# Sheet1.net
KiCad netlist of a schematic drawn in Altium Designer
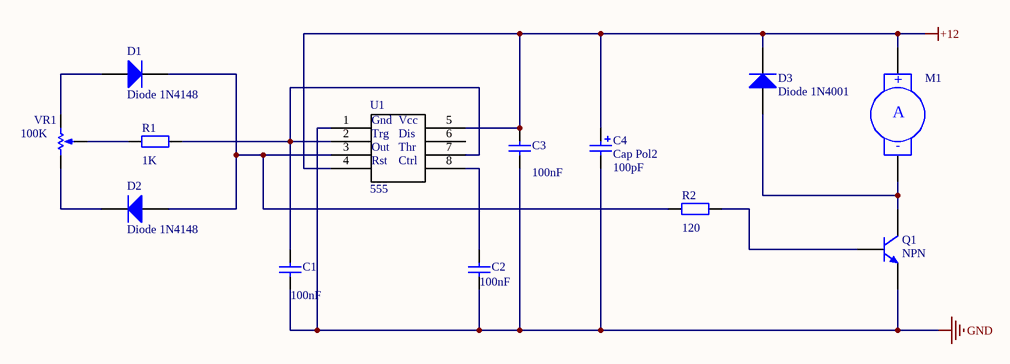
[diagram p0: Sheet1.SchDoc]

(export (version "E")
  (design (tool "Eeschema 10.0.6"))
  (components
    (comp (ref "C1")
      (value "100nF")
      (footprint "RAD-0.3")
      (description "Capacitor")
      (fields (field (name "Comment") "Cap") (field (name "PUBLISHER") "Altium Limited"))
      (libsource (lib "Miscellaneous Devices") (part "Cap"))
    )
    (comp (ref "C2")
      (value "100nF")
      (footprint "RAD-0.3")
      (description "Capacitor")
      (fields (field (name "Comment") "Cap") (field (name "PUBLISHER") "Altium Limited"))
      (libsource (lib "Miscellaneous Devices") (part "Cap"))
    )
    (comp (ref "C3")
      (value "100nF")
      (footprint "RAD-0.3")
      (description "Capacitor")
      (fields (field (name "Comment") "Cap") (field (name "PUBLISHER") "Altium Limited"))
      (libsource (lib "Miscellaneous Devices") (part "Cap"))
    )
    (comp (ref "C4")
      (value "Cap Pol2")
      (footprint "POLAR0.8")
      (description "Polarized Capacitor (Axial)")
      (fields (field (name "ALTIUM_VALUE") "100pF") (field (name "PUBLISHER") "Altium Limited"))
      (libsource (lib "Miscellaneous Devices") (part "Cap Pol2"))
    )
    (comp (ref "D1")
      (value "Diode 1N4148")
      (footprint "DO-35")
      (description "High Conductance Fast Diode")
      (fields (field (name "PUBLISHER") "Altium Limited"))
      (libsource (lib "Miscellaneous Devices") (part "Diode 1N4148"))
    )
    (comp (ref "D2")
      (value "Diode 1N4148")
      (footprint "DO-35")
      (description "High Conductance Fast Diode")
      (fields (field (name "PUBLISHER") "Altium Limited"))
      (libsource (lib "Miscellaneous Devices") (part "Diode 1N4148"))
    )
    (comp (ref "D3")
      (value "Diode 1N4001")
      (footprint "DO-41")
      (description "1 Amp General Purpose Rectifier")
      (fields (field (name "PUBLISHER") "Altium Limited"))
      (libsource (lib "Miscellaneous Devices") (part "Diode 1N4001"))
    )
    (comp (ref "M1")
      (value "Motor Servo")
      (footprint "RAD-0.4")
      (description "Servo Motor")
      (fields (field (name "PUBLISHER") "Altium Limited"))
      (libsource (lib "Miscellaneous Devices") (part "Motor Servo"))
    )
    (comp (ref "Q1")
      (value "NPN")
      (footprint "TO-226-AA")
      (description "NPN Bipolar Transistor")
      (fields (field (name "PUBLISHER") "Altium Limited"))
      (libsource (lib "Miscellaneous Devices") (part "NPN"))
    )
    (comp (ref "R1")
      (value "1K")
      (footprint "AXIAL-0.4")
      (description "Resistor")
      (fields (field (name "Comment") "Res2") (field (name "PUBLISHER") "Altium Limited"))
      (libsource (lib "Miscellaneous Devices") (part "Res2"))
    )
    (comp (ref "R2")
      (value "120")
      (footprint "AXIAL-0.4")
      (description "Resistor")
      (fields (field (name "Comment") "Res2") (field (name "PUBLISHER") "Altium Limited"))
      (libsource (lib "Miscellaneous Devices") (part "Res2"))
    )
    (comp (ref "U1") (value "555") (footprint "PCBComponent_1") (libsource (lib "Schlib1") (part "555")))
    (comp (ref "VR1")
      (value "100K")
      (footprint "VR5")
      (description "Potentiometer")
      (fields (field (name "Comment") "RPot") (field (name "PUBLISHER") "Altium Limited"))
      (libsource (lib "Miscellaneous Devices") (part "RPot"))
    )
  )
  (nets
    (net (code "1") (name "+12") (class "Default")
      (node (ref "C3") (pin "2") (pinfunction "2_2") (pintype "passive"))
      (node (ref "C4") (pin "1") (pinfunction "1_1") (pintype "passive"))
      (node (ref "D3") (pin "2") (pinfunction "K_2") (pintype "passive"))
      (node (ref "M1") (pin "1") (pinfunction "+_1") (pintype "passive"))
    )
    (net (code "2") (name "GND") (class "Default")
      (node (ref "C1") (pin "1") (pinfunction "1_1") (pintype "passive"))
      (node (ref "C2") (pin "1") (pinfunction "1_1") (pintype "passive"))
      (node (ref "C3") (pin "1") (pinfunction "1_1") (pintype "passive"))
      (node (ref "C4") (pin "2") (pinfunction "2_2") (pintype "passive"))
      (node (ref "Q1") (pin "3") (pinfunction "E_3") (pintype "passive"))
    )
    (net (code "3") (name "Net-(C1-Pad2)") (class "Default")
      (node (ref "C1") (pin "2") (pinfunction "2_2") (pintype "passive"))
      (node (ref "R1") (pin "2") (pinfunction "2_2") (pintype "passive"))
    )
    (net (code "4") (name "Net-(D1-A)") (class "Default")
      (node (ref "D1") (pin "1") (pinfunction "A_1") (pintype "passive"))
      (node (ref "VR1") (pin "2") (pinfunction "BOT_2") (pintype "passive"))
    )
    (net (code "5") (name "Net-(D1-K)") (class "Default")
      (node (ref "D1") (pin "2") (pinfunction "K_2") (pintype "passive"))
      (node (ref "D2") (pin "1") (pinfunction "A_1") (pintype "passive"))
      (node (ref "R2") (pin "1") (pinfunction "1_1") (pintype "passive"))
    )
    (net (code "6") (name "Net-(D2-K)") (class "Default")
      (node (ref "D2") (pin "2") (pinfunction "K_2") (pintype "passive"))
      (node (ref "VR1") (pin "1") (pinfunction "TOP_1") (pintype "passive"))
    )
    (net (code "7") (name "Net-(D3-A)") (class "Default")
      (node (ref "D3") (pin "1") (pinfunction "A_1") (pintype "passive"))
      (node (ref "M1") (pin "2") (pinfunction "-_2") (pintype "passive"))
      (node (ref "Q1") (pin "1") (pinfunction "C_1") (pintype "passive"))
    )
    (net (code "8") (name "Net-(Q1-B)") (class "Default")
      (node (ref "Q1") (pin "2") (pinfunction "B_2") (pintype "passive"))
      (node (ref "R2") (pin "2") (pinfunction "2_2") (pintype "passive"))
    )
    (net (code "9") (name "Net-(VR1-TAP)") (class "Default")
      (node (ref "R1") (pin "1") (pinfunction "1_1") (pintype "passive"))
      (node (ref "VR1") (pin "3") (pinfunction "TAP_3") (pintype "passive"))
    )
    (net (code "10") (name "unconnected-(C2-Pad2)") (class "Default")
      (node (ref "C2") (pin "2") (pinfunction "2_2") (pintype "passive"))
    )
    (net (code "11") (name "unconnected-(U1-0-Pad1)") (class "Default")
      (node (ref "U1") (pin "1") (pinfunction "0_1") (pintype "passive"))
    )
    (net (code "12") (name "unconnected-(U1-1-Pad2)") (class "Default")
      (node (ref "U1") (pin "2") (pinfunction "1_2") (pintype "passive"))
    )
    (net (code "13") (name "unconnected-(U1-2-Pad3)") (class "Default")
      (node (ref "U1") (pin "3") (pinfunction "2_3") (pintype "passive"))
    )
    (net (code "14") (name "unconnected-(U1-3-Pad4)") (class "Default")
      (node (ref "U1") (pin "4") (pinfunction "3_4") (pintype "passive"))
    )
    (net (code "15") (name "unconnected-(U1-4-Pad5)") (class "Default")
      (node (ref "U1") (pin "5") (pinfunction "4_5") (pintype "passive"))
    )
    (net (code "16") (name "unconnected-(U1-5-Pad6)") (class "Default")
      (node (ref "U1") (pin "6") (pinfunction "5_6") (pintype "passive"))
    )
    (net (code "17") (name "unconnected-(U1-6-Pad7)") (class "Default")
      (node (ref "U1") (pin "7") (pinfunction "6_7") (pintype "passive"))
    )
    (net (code "18") (name "unconnected-(U1-7-Pad8)") (class "Default")
      (node (ref "U1") (pin "8") (pinfunction "7_8") (pintype "passive"))
    )
  )
)
